# Main.net
KiCad netlist of a schematic drawn in EAGLE
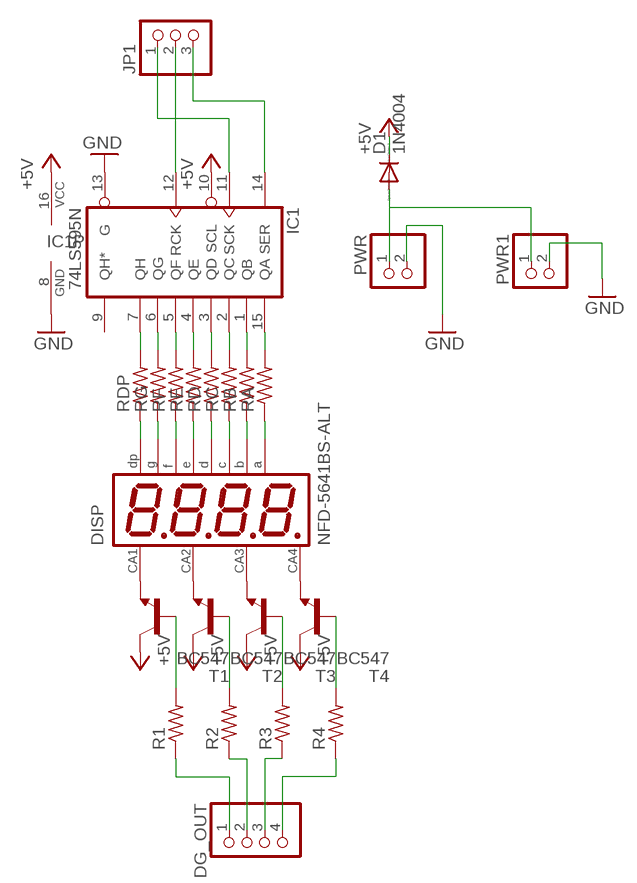
[diagram p0: schematic, sheet 1]

(export (version "E")
  (design (tool "Eeschema 10.0.6"))
  (components
    (comp (ref "D1")
      (value "1N4004")
      (footprint "eagle-import:DO41-10")
      (libsource (lib "eagle-import") (part "1N4004"))
    )
    (comp (ref "DG_OUT")
      (value "PINHD-1X4")
      (footprint "eagle-import:1X04")
      (libsource (lib "eagle-import") (part "PINHD-1X4"))
    )
    (comp (ref "DISP")
      (value "NFD-5641BS-ALT")
      (footprint "eagle-import:NFD-5641")
      (libsource (lib "eagle-import") (part "NFD-5641BS-ALT"))
    )
    (comp (ref "IC1")
      (value "74LS595N")
      (footprint "eagle-import:DIL16")
      (libsource (lib "eagle-import") (part "74595NLS"))
    )
    (comp (ref "JP1")
      (value "PINHD-1X3")
      (footprint "eagle-import:1X03")
      (libsource (lib "eagle-import") (part "PINHD-1X3"))
    )
    (comp (ref "PWR")
      (value "PINHD-1X2")
      (footprint "eagle-import:1X02")
      (libsource (lib "eagle-import") (part "PINHD-1X2"))
    )
    (comp (ref "PWR1")
      (value "PINHD-1X2")
      (footprint "eagle-import:1X02")
      (libsource (lib "eagle-import") (part "PINHD-1X2"))
    )
    (comp (ref "R1")
      (value "R-US_0309/12")
      (footprint "eagle-import:0309_12")
      (libsource (lib "eagle-import") (part "R-US_0309/12"))
    )
    (comp (ref "R2")
      (value "R-US_0309/12")
      (footprint "eagle-import:0309_12")
      (libsource (lib "eagle-import") (part "R-US_0309/12"))
    )
    (comp (ref "R3")
      (value "R-US_0309/12")
      (footprint "eagle-import:0309_12")
      (libsource (lib "eagle-import") (part "R-US_0309/12"))
    )
    (comp (ref "R4")
      (value "R-US_0309/12")
      (footprint "eagle-import:0309_12")
      (libsource (lib "eagle-import") (part "R-US_0309/12"))
    )
    (comp (ref "RA")
      (value "R-US_0309/12")
      (footprint "eagle-import:0309_12")
      (libsource (lib "eagle-import") (part "R-US_0309/12"))
    )
    (comp (ref "RB")
      (value "R-US_0309/12")
      (footprint "eagle-import:0309_12")
      (libsource (lib "eagle-import") (part "R-US_0309/12"))
    )
    (comp (ref "RC")
      (value "R-US_0309/12")
      (footprint "eagle-import:0309_12")
      (libsource (lib "eagle-import") (part "R-US_0309/12"))
    )
    (comp (ref "RD")
      (value "R-US_0309/12")
      (footprint "eagle-import:0309_12")
      (libsource (lib "eagle-import") (part "R-US_0309/12"))
    )
    (comp (ref "RDP")
      (value "R-US_0309/12")
      (footprint "eagle-import:0309_12")
      (libsource (lib "eagle-import") (part "R-US_0309/12"))
    )
    (comp (ref "RE")
      (value "R-US_0309/12")
      (footprint "eagle-import:0309_12")
      (libsource (lib "eagle-import") (part "R-US_0309/12"))
    )
    (comp (ref "RF")
      (value "R-US_0309/12")
      (footprint "eagle-import:0309_12")
      (libsource (lib "eagle-import") (part "R-US_0309/12"))
    )
    (comp (ref "RG")
      (value "R-US_0309/12")
      (footprint "eagle-import:0309_12")
      (libsource (lib "eagle-import") (part "R-US_0309/12"))
    )
    (comp (ref "T1")
      (value "BC547")
      (footprint "eagle-import:TO92")
      (libsource (lib "eagle-import") (part "BC547"))
    )
    (comp (ref "T2")
      (value "BC547")
      (footprint "eagle-import:TO92")
      (libsource (lib "eagle-import") (part "BC547"))
    )
    (comp (ref "T3")
      (value "BC547")
      (footprint "eagle-import:TO92")
      (libsource (lib "eagle-import") (part "BC547"))
    )
    (comp (ref "T4")
      (value "BC547")
      (footprint "eagle-import:TO92")
      (libsource (lib "eagle-import") (part "BC547"))
    )
  )
  (nets
    (net (code "1") (name "+5V") (class "Default")
      (node (ref "D1") (pin "C") (pinfunction "C_C") (pintype "passive"))
      (node (ref "IC1") (pin "10") (pinfunction "SCL_10") (pintype "input"))
      (node (ref "IC1") (pin "16") (pinfunction "VCC_16") (pintype "power_in"))
      (node (ref "T1") (pin "3") (pinfunction "C_3") (pintype "passive"))
      (node (ref "T2") (pin "3") (pinfunction "C_3") (pintype "passive"))
      (node (ref "T3") (pin "3") (pinfunction "C_3") (pintype "passive"))
      (node (ref "T4") (pin "3") (pinfunction "C_3") (pintype "passive"))
    )
    (net (code "2") (name "GND") (class "Default")
      (node (ref "IC1") (pin "13") (pinfunction "G_13") (pintype "input"))
      (node (ref "IC1") (pin "8") (pinfunction "GND_8") (pintype "power_in"))
      (node (ref "PWR") (pin "2") (pinfunction "2_2") (pintype "passive"))
      (node (ref "PWR1") (pin "2") (pinfunction "2_2") (pintype "passive"))
    )
    (net (code "3") (name "Net-(D1-PadA)") (class "Default")
      (node (ref "D1") (pin "A") (pinfunction "A_A") (pintype "passive"))
      (node (ref "PWR") (pin "1") (pinfunction "1_1") (pintype "passive"))
      (node (ref "PWR1") (pin "1") (pinfunction "1_1") (pintype "passive"))
    )
    (net (code "4") (name "Net-(DG_OUT-Pad1)") (class "Default")
      (node (ref "DG_OUT") (pin "1") (pinfunction "1_1") (pintype "passive"))
      (node (ref "R1") (pin "1") (pinfunction "1_1") (pintype "passive"))
    )
    (net (code "5") (name "Net-(DG_OUT-Pad2)") (class "Default")
      (node (ref "DG_OUT") (pin "2") (pinfunction "2_2") (pintype "passive"))
      (node (ref "R2") (pin "1") (pinfunction "1_1") (pintype "passive"))
    )
    (net (code "6") (name "Net-(DG_OUT-Pad3)") (class "Default")
      (node (ref "DG_OUT") (pin "3") (pinfunction "3_3") (pintype "passive"))
      (node (ref "R3") (pin "1") (pinfunction "1_1") (pintype "passive"))
    )
    (net (code "7") (name "Net-(DG_OUT-Pad4)") (class "Default")
      (node (ref "DG_OUT") (pin "4") (pinfunction "4_4") (pintype "passive"))
      (node (ref "R4") (pin "1") (pinfunction "1_1") (pintype "passive"))
    )
    (net (code "8") (name "Net-(DISP-PadP$1)") (class "Default")
      (node (ref "DISP") (pin "P$1") (pinfunction "P$1_P$1") (pintype "bidirectional"))
      (node (ref "RE") (pin "1") (pinfunction "1_1") (pintype "passive"))
    )
    (net (code "9") (name "Net-(DISP-PadP$2)") (class "Default")
      (node (ref "DISP") (pin "P$2") (pinfunction "P$2_P$2") (pintype "bidirectional"))
      (node (ref "RD") (pin "1") (pinfunction "1_1") (pintype "passive"))
    )
    (net (code "10") (name "Net-(DISP-PadP$3)") (class "Default")
      (node (ref "DISP") (pin "P$3") (pinfunction "P$3_P$3") (pintype "bidirectional"))
      (node (ref "RDP") (pin "1") (pinfunction "1_1") (pintype "passive"))
    )
    (net (code "11") (name "Net-(DISP-PadP$4)") (class "Default")
      (node (ref "DISP") (pin "P$4") (pinfunction "P$4_P$4") (pintype "bidirectional"))
      (node (ref "RC") (pin "1") (pinfunction "1_1") (pintype "passive"))
    )
    (net (code "12") (name "Net-(DISP-PadP$5)") (class "Default")
      (node (ref "DISP") (pin "P$5") (pinfunction "P$5_P$5") (pintype "bidirectional"))
      (node (ref "RG") (pin "1") (pinfunction "1_1") (pintype "passive"))
    )
    (net (code "13") (name "Net-(DISP-PadP$7)") (class "Default")
      (node (ref "DISP") (pin "P$7") (pinfunction "P$7_P$7") (pintype "bidirectional"))
      (node (ref "RB") (pin "1") (pinfunction "1_1") (pintype "passive"))
    )
    (net (code "14") (name "Net-(DISP-PadP$10)") (class "Default")
      (node (ref "DISP") (pin "P$10") (pinfunction "P$10_P$10") (pintype "bidirectional"))
      (node (ref "RF") (pin "1") (pinfunction "1_1") (pintype "passive"))
    )
    (net (code "15") (name "Net-(DISP-PadP$11)") (class "Default")
      (node (ref "DISP") (pin "P$11") (pinfunction "P$11_P$11") (pintype "bidirectional"))
      (node (ref "RA") (pin "1") (pinfunction "1_1") (pintype "passive"))
    )
    (net (code "16") (name "Net-(IC1A-QA)") (class "Default")
      (node (ref "IC1") (pin "15") (pinfunction "QA_15") (pintype "tri_state"))
      (node (ref "RA") (pin "2") (pinfunction "2_2") (pintype "passive"))
    )
    (net (code "17") (name "Net-(IC1A-QB)") (class "Default")
      (node (ref "IC1") (pin "1") (pinfunction "QB_1") (pintype "tri_state"))
      (node (ref "RB") (pin "2") (pinfunction "2_2") (pintype "passive"))
    )
    (net (code "18") (name "Net-(IC1A-QC)") (class "Default")
      (node (ref "IC1") (pin "2") (pinfunction "QC_2") (pintype "tri_state"))
      (node (ref "RC") (pin "2") (pinfunction "2_2") (pintype "passive"))
    )
    (net (code "19") (name "Net-(IC1A-QD)") (class "Default")
      (node (ref "IC1") (pin "3") (pinfunction "QD_3") (pintype "tri_state"))
      (node (ref "RD") (pin "2") (pinfunction "2_2") (pintype "passive"))
    )
    (net (code "20") (name "Net-(IC1A-QE)") (class "Default")
      (node (ref "IC1") (pin "4") (pinfunction "QE_4") (pintype "tri_state"))
      (node (ref "RE") (pin "2") (pinfunction "2_2") (pintype "passive"))
    )
    (net (code "21") (name "Net-(IC1A-QF)") (class "Default")
      (node (ref "IC1") (pin "5") (pinfunction "QF_5") (pintype "tri_state"))
      (node (ref "RF") (pin "2") (pinfunction "2_2") (pintype "passive"))
    )
    (net (code "22") (name "Net-(IC1A-QG)") (class "Default")
      (node (ref "IC1") (pin "6") (pinfunction "QG_6") (pintype "tri_state"))
      (node (ref "RG") (pin "2") (pinfunction "2_2") (pintype "passive"))
    )
    (net (code "23") (name "Net-(IC1A-QH)") (class "Default")
      (node (ref "IC1") (pin "7") (pinfunction "QH_7") (pintype "tri_state"))
      (node (ref "RDP") (pin "2") (pinfunction "2_2") (pintype "passive"))
    )
    (net (code "24") (name "Net-(IC1A-RCK)") (class "Default")
      (node (ref "IC1") (pin "12") (pinfunction "RCK_12") (pintype "input"))
      (node (ref "JP1") (pin "2") (pinfunction "2_2") (pintype "passive"))
    )
    (net (code "25") (name "Net-(IC1A-SCK)") (class "Default")
      (node (ref "IC1") (pin "11") (pinfunction "SCK_11") (pintype "input"))
      (node (ref "JP1") (pin "1") (pinfunction "1_1") (pintype "passive"))
    )
    (net (code "26") (name "Net-(IC1A-SER)") (class "Default")
      (node (ref "IC1") (pin "14") (pinfunction "SER_14") (pintype "input"))
      (node (ref "JP1") (pin "3") (pinfunction "3_3") (pintype "passive"))
    )
    (net (code "27") (name "Net-(T1-B)") (class "Default")
      (node (ref "R1") (pin "2") (pinfunction "2_2") (pintype "passive"))
      (node (ref "T1") (pin "2") (pinfunction "B_2") (pintype "passive"))
    )
    (net (code "28") (name "Net-(T1-E)") (class "Default")
      (node (ref "DISP") (pin "P$12") (pinfunction "P$12_P$12") (pintype "bidirectional"))
      (node (ref "T1") (pin "1") (pinfunction "E_1") (pintype "passive"))
    )
    (net (code "29") (name "Net-(T2-B)") (class "Default")
      (node (ref "R2") (pin "2") (pinfunction "2_2") (pintype "passive"))
      (node (ref "T2") (pin "2") (pinfunction "B_2") (pintype "passive"))
    )
    (net (code "30") (name "Net-(T2-E)") (class "Default")
      (node (ref "DISP") (pin "P$9") (pinfunction "P$9_P$9") (pintype "bidirectional"))
      (node (ref "T2") (pin "1") (pinfunction "E_1") (pintype "passive"))
    )
    (net (code "31") (name "Net-(T3-B)") (class "Default")
      (node (ref "R3") (pin "2") (pinfunction "2_2") (pintype "passive"))
      (node (ref "T3") (pin "2") (pinfunction "B_2") (pintype "passive"))
    )
    (net (code "32") (name "Net-(T3-E)") (class "Default")
      (node (ref "DISP") (pin "P$8") (pinfunction "P$8_P$8") (pintype "bidirectional"))
      (node (ref "T3") (pin "1") (pinfunction "E_1") (pintype "passive"))
    )
    (net (code "33") (name "Net-(T4-B)") (class "Default")
      (node (ref "R4") (pin "2") (pinfunction "2_2") (pintype "passive"))
      (node (ref "T4") (pin "2") (pinfunction "B_2") (pintype "passive"))
    )
    (net (code "34") (name "Net-(T4-E)") (class "Default")
      (node (ref "DISP") (pin "P$6") (pinfunction "P$6_P$6") (pintype "bidirectional"))
      (node (ref "T4") (pin "1") (pinfunction "E_1") (pintype "passive"))
    )
    (net (code "35") (name "unconnected-(IC1A-QH*-Pad9)") (class "Default")
      (node (ref "IC1") (pin "9") (pinfunction "QH*_9") (pintype "tri_state"))
    )
  )
)
